# TOPCPCB.net
KiCad netlist of a schematic drawn in EAGLE
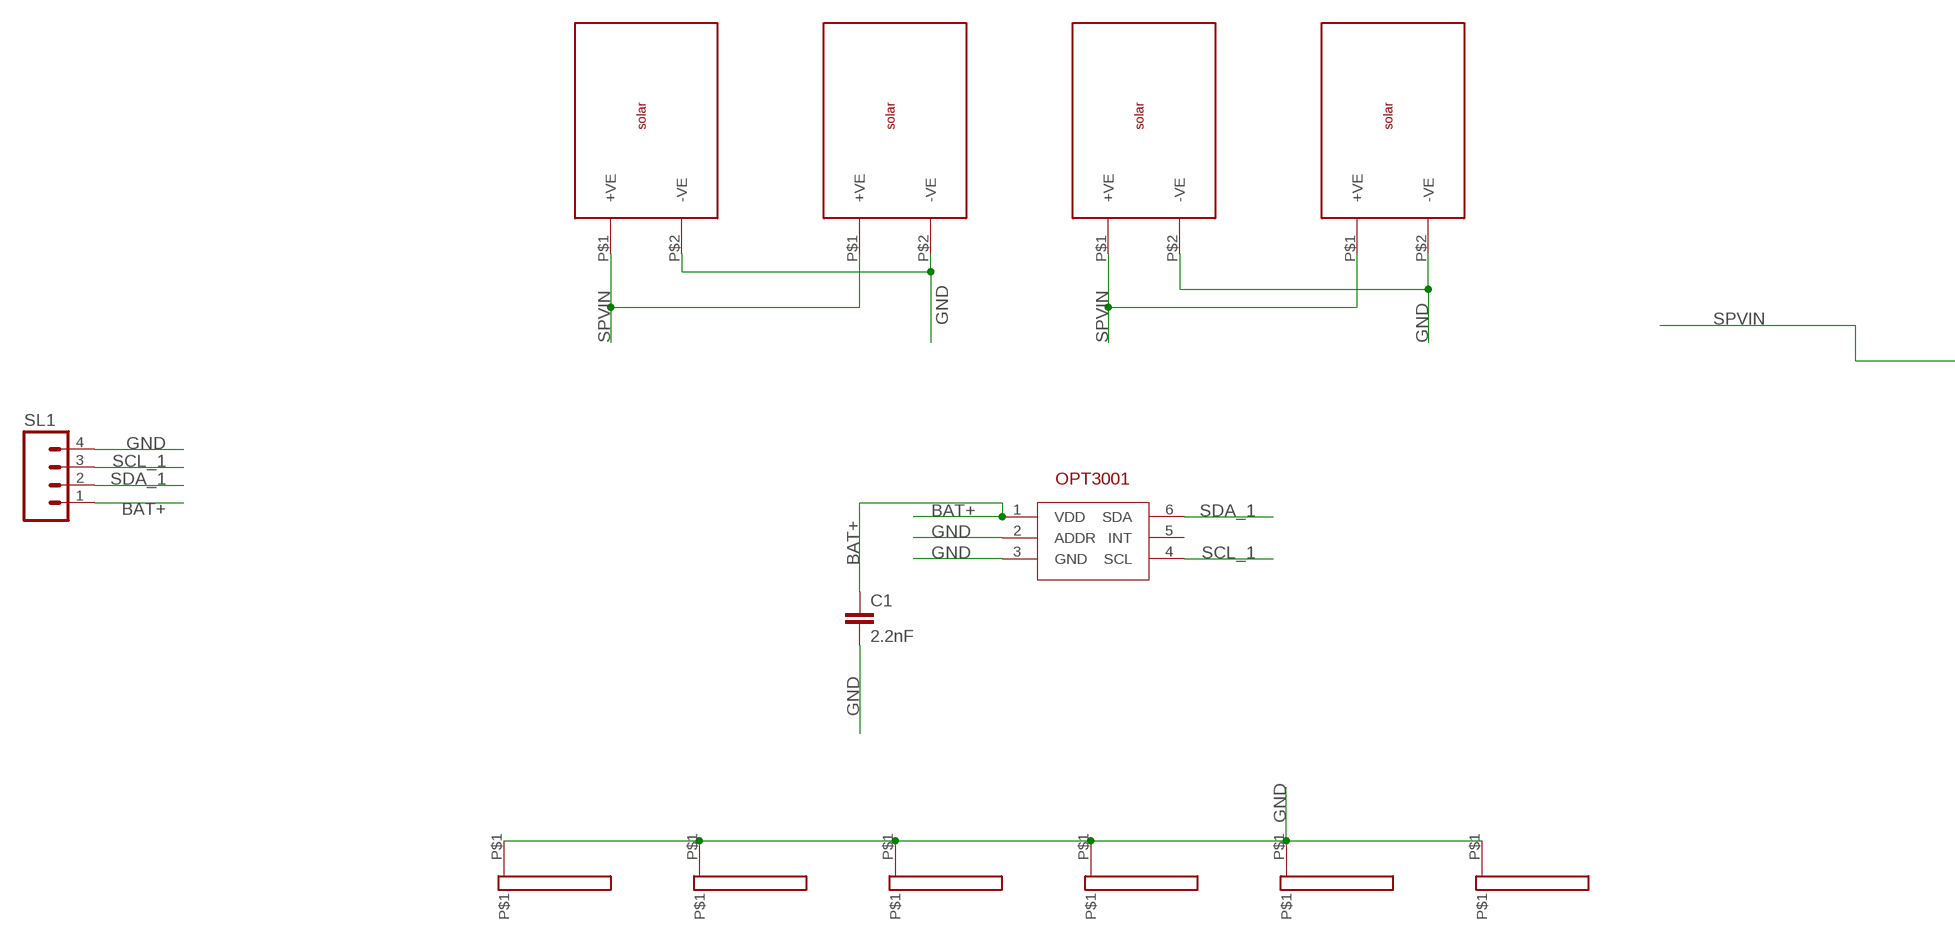
[diagram p0: schematic, sheet 1, part 1 of 2]
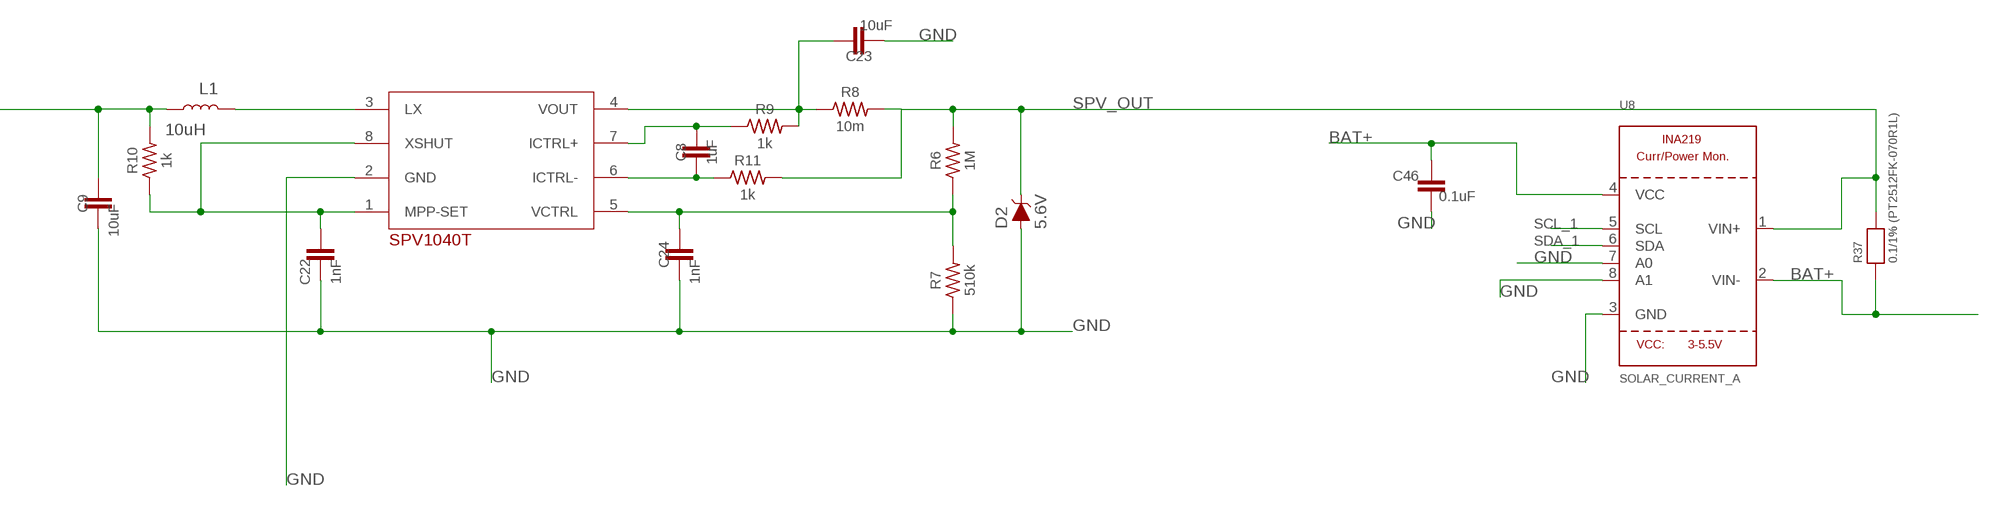
[diagram p1: schematic, sheet 1, part 2 of 2]

(export (version "E")
  (design (tool "Eeschema 10.0.6"))
  (components
    (comp (ref "C1")
      (value "2.2nF")
      (footprint "eagle-import:0603")
      (libsource (lib "eagle-import") (part "2.2NF/2200PF-0603-50V-10%"))
    )
    (comp (ref "C8")
      (value "1uF")
      (footprint "eagle-import:0603")
      (libsource (lib "eagle-import") (part "10UF-0603-6.3V-20%"))
    )
    (comp (ref "C9")
      (value "10uF")
      (footprint "eagle-import:0603")
      (libsource (lib "eagle-import") (part "10UF-0603-6.3V-20%"))
    )
    (comp (ref "C22")
      (value "1nF")
      (footprint "eagle-import:0603")
      (libsource (lib "eagle-import") (part "10UF-0603-6.3V-20%"))
    )
    (comp (ref "C23")
      (value "10uF")
      (footprint "eagle-import:0603")
      (libsource (lib "eagle-import") (part "10UF-0603-6.3V-20%"))
    )
    (comp (ref "C24")
      (value "1nF")
      (footprint "eagle-import:0603")
      (libsource (lib "eagle-import") (part "10UF-0603-6.3V-20%"))
    )
    (comp (ref "C46")
      (value "0.1uF")
      (footprint "eagle-import:0603")
      (libsource (lib "eagle-import") (part "10UF-0603-6.3V-20%"))
    )
    (comp (ref "D2")
      (value "5.6V")
      (footprint "eagle-import:SOD-323")
      (libsource (lib "eagle-import") (part "DIODE-ZENER-MMSZ5232BS"))
    )
    (comp (ref "L1")
      (value "10uH")
      (footprint "eagle-import:0603")
      (libsource (lib "eagle-import") (part "INDUCTOR-0603-33NH"))
    )
    (comp (ref "LEFTSOLD")
      (value "16X2")
      (footprint "eagle-import:16X2")
      (libsource (lib "eagle-import") (part "16X2"))
    )
    (comp (ref "R6")
      (value "1M")
      (footprint "eagle-import:RES_0603")
      (fields
        (field (name "DIGIKEY_PART_NUMBER") "311-0.0GRTR-ND")
        (field (name "MANUFACTURER") "Yageo")
        (field (name "MPN") "RC0603JR-070RL")
        (field (name "CREATED_BY") "PCBLayout.com")
      )
      (libsource (lib "eagle-import") (part "RC0603JR-070RL"))
    )
    (comp (ref "R7")
      (value "510k")
      (footprint "eagle-import:RES_0603")
      (fields
        (field (name "DIGIKEY_PART_NUMBER") "311-0.0GRTR-ND")
        (field (name "MANUFACTURER") "Yageo")
        (field (name "MPN") "RC0603JR-070RL")
        (field (name "CREATED_BY") "PCBLayout.com")
      )
      (libsource (lib "eagle-import") (part "RC0603JR-070RL"))
    )
    (comp (ref "R8")
      (value "10m")
      (footprint "eagle-import:RES_0603")
      (fields
        (field (name "DIGIKEY_PART_NUMBER") "311-0.0GRTR-ND")
        (field (name "MANUFACTURER") "Yageo")
        (field (name "MPN") "RC0603JR-070RL")
        (field (name "CREATED_BY") "PCBLayout.com")
      )
      (libsource (lib "eagle-import") (part "RC0603JR-070RL"))
    )
    (comp (ref "R9")
      (value "1k")
      (footprint "eagle-import:RES_0603")
      (fields
        (field (name "DIGIKEY_PART_NUMBER") "311-0.0GRTR-ND")
        (field (name "MANUFACTURER") "Yageo")
        (field (name "MPN") "RC0603JR-070RL")
        (field (name "CREATED_BY") "PCBLayout.com")
      )
      (libsource (lib "eagle-import") (part "RC0603JR-070RL"))
    )
    (comp (ref "R10")
      (value "1k")
      (footprint "eagle-import:RES_0603")
      (fields
        (field (name "DIGIKEY_PART_NUMBER") "311-0.0GRTR-ND")
        (field (name "MANUFACTURER") "Yageo")
        (field (name "MPN") "RC0603JR-070RL")
        (field (name "CREATED_BY") "PCBLayout.com")
      )
      (libsource (lib "eagle-import") (part "RC0603JR-070RL"))
    )
    (comp (ref "R11")
      (value "1k")
      (footprint "eagle-import:RES_0603")
      (fields
        (field (name "DIGIKEY_PART_NUMBER") "311-0.0GRTR-ND")
        (field (name "MANUFACTURER") "Yageo")
        (field (name "MPN") "RC0603JR-070RL")
        (field (name "CREATED_BY") "PCBLayout.com")
      )
      (libsource (lib "eagle-import") (part "RC0603JR-070RL"))
    )
    (comp (ref "R37")
      (value "0.1/1% (PT2512FK-070R1L)")
      (footprint "eagle-import:2512")
      (libsource (lib "eagle-import") (part "RESISTOR2512"))
    )
    (comp (ref "SL1")
      (value "M04")
      (footprint "eagle-import:04P")
      (libsource (lib "eagle-import") (part "M04"))
    )
    (comp (ref "SPV_A")
      (value "SPV1040T_")
      (footprint "eagle-import:SOP65P640X120-8N")
      (libsource (lib "eagle-import") (part "SPV1040T_"))
    )
    (comp (ref "U$1")
      (value "16X2")
      (footprint "eagle-import:16X2")
      (libsource (lib "eagle-import") (part "16X2"))
    )
    (comp (ref "U$4")
      (value "16X2")
      (footprint "eagle-import:16X2")
      (libsource (lib "eagle-import") (part "16X2"))
    )
    (comp (ref "U$5")
      (value "16X2")
      (footprint "eagle-import:16X2")
      (libsource (lib "eagle-import") (part "16X2"))
    )
    (comp (ref "U$7")
      (value "16X2")
      (footprint "eagle-import:16X2")
      (libsource (lib "eagle-import") (part "16X2"))
    )
    (comp (ref "U$9")
      (value "16X2")
      (footprint "eagle-import:16X2")
      (libsource (lib "eagle-import") (part "16X2"))
    )
    (comp (ref "U$10")
      (value "SOLAR_50_5_2")
      (footprint "eagle-import:FOOT")
      (libsource (lib "eagle-import") (part "SOLAR_50_5_2"))
    )
    (comp (ref "U$11")
      (value "SOLAR_50_5_2")
      (footprint "eagle-import:FOOT")
      (libsource (lib "eagle-import") (part "SOLAR_50_5_2"))
    )
    (comp (ref "U$12")
      (value "SOLAR_50_5_2")
      (footprint "eagle-import:FOOT")
      (libsource (lib "eagle-import") (part "SOLAR_50_5_2"))
    )
    (comp (ref "U$13")
      (value "SOLAR_50_5_2")
      (footprint "eagle-import:FOOT")
      (libsource (lib "eagle-import") (part "SOLAR_50_5_2"))
    )
    (comp (ref "U1")
      (value "SON65P200X200X65-7N")
      (footprint "eagle-import:SON65P200X200X65-7N")
      (fields (field (name "MANUFACTURER") "Maxim Integrated"))
      (libsource (lib "eagle-import") (part "SON65P200X200X65-7N"))
    )
    (comp (ref "U8")
      (value "SOLAR_CURRENT_A")
      (footprint "eagle-import:SOT23-8")
      (libsource (lib "eagle-import") (part "INA219"))
    )
  )
  (nets
    (net (code "1") (name "/BAT+") (class "Default")
      (node (ref "C1") (pin "1") (pinfunction "1_1") (pintype "passive"))
      (node (ref "C46") (pin "1") (pinfunction "1_1") (pintype "passive"))
      (node (ref "R37") (pin "1") (pinfunction "1_1") (pintype "passive"))
      (node (ref "SL1") (pin "1") (pinfunction "1_1") (pintype "passive"))
      (node (ref "U1") (pin "1") (pinfunction "VDD_1") (pintype "bidirectional"))
      (node (ref "U8") (pin "2") (pinfunction "VIN-_2") (pintype "bidirectional"))
      (node (ref "U8") (pin "4") (pinfunction "VCC_4") (pintype "bidirectional"))
    )
    (net (code "2") (name "/GND") (class "Default")
      (node (ref "C1") (pin "2") (pinfunction "2_2") (pintype "passive"))
      (node (ref "C22") (pin "2") (pinfunction "2_2") (pintype "passive"))
      (node (ref "C23") (pin "2") (pinfunction "2_2") (pintype "passive"))
      (node (ref "C24") (pin "2") (pinfunction "2_2") (pintype "passive"))
      (node (ref "C46") (pin "2") (pinfunction "2_2") (pintype "passive"))
      (node (ref "C9") (pin "2") (pinfunction "2_2") (pintype "passive"))
      (node (ref "D2") (pin "A") (pinfunction "A_A") (pintype "passive"))
      (node (ref "LEFTSOLD") (pin "P$1") (pinfunction "P$1_P$1") (pintype "bidirectional"))
      (node (ref "R7") (pin "1") (pinfunction "1_1") (pintype "passive"))
      (node (ref "SL1") (pin "4") (pinfunction "4_4") (pintype "passive"))
      (node (ref "SPV_A") (pin "2") (pinfunction "GND_2") (pintype "bidirectional"))
      (node (ref "U$1") (pin "P$1") (pinfunction "P$1_P$1") (pintype "bidirectional"))
      (node (ref "U$10") (pin "P$2") (pinfunction "-VE_P$2") (pintype "bidirectional"))
      (node (ref "U$11") (pin "P$2") (pinfunction "-VE_P$2") (pintype "bidirectional"))
      (node (ref "U$12") (pin "P$2") (pinfunction "-VE_P$2") (pintype "bidirectional"))
      (node (ref "U$13") (pin "P$2") (pinfunction "-VE_P$2") (pintype "bidirectional"))
      (node (ref "U$4") (pin "P$1") (pinfunction "P$1_P$1") (pintype "bidirectional"))
      (node (ref "U$5") (pin "P$1") (pinfunction "P$1_P$1") (pintype "bidirectional"))
      (node (ref "U$7") (pin "P$1") (pinfunction "P$1_P$1") (pintype "bidirectional"))
      (node (ref "U$9") (pin "P$1") (pinfunction "P$1_P$1") (pintype "bidirectional"))
      (node (ref "U1") (pin "2") (pinfunction "ADDR_2") (pintype "bidirectional"))
      (node (ref "U1") (pin "3") (pinfunction "GND_3") (pintype "bidirectional"))
      (node (ref "U8") (pin "3") (pinfunction "GND_3") (pintype "bidirectional"))
      (node (ref "U8") (pin "7") (pinfunction "A0_7") (pintype "bidirectional"))
      (node (ref "U8") (pin "8") (pinfunction "A1_8") (pintype "bidirectional"))
    )
    (net (code "3") (name "/SCL_1") (class "Default")
      (node (ref "SL1") (pin "3") (pinfunction "3_3") (pintype "passive"))
      (node (ref "U1") (pin "4") (pinfunction "SCL_4") (pintype "bidirectional"))
      (node (ref "U8") (pin "5") (pinfunction "SCL_5") (pintype "bidirectional"))
    )
    (net (code "4") (name "/SDA_1") (class "Default")
      (node (ref "SL1") (pin "2") (pinfunction "2_2") (pintype "passive"))
      (node (ref "U1") (pin "6") (pinfunction "SDA_6") (pintype "bidirectional"))
      (node (ref "U8") (pin "6") (pinfunction "SDA_6") (pintype "bidirectional"))
    )
    (net (code "5") (name "/SPVIN") (class "Default")
      (node (ref "C9") (pin "1") (pinfunction "1_1") (pintype "passive"))
      (node (ref "L1") (pin "1") (pinfunction "1_1") (pintype "passive"))
      (node (ref "R10") (pin "2") (pinfunction "2_2") (pintype "passive"))
      (node (ref "U$10") (pin "P$1") (pinfunction "+VE_P$1") (pintype "bidirectional"))
      (node (ref "U$11") (pin "P$1") (pinfunction "+VE_P$1") (pintype "bidirectional"))
      (node (ref "U$12") (pin "P$1") (pinfunction "+VE_P$1") (pintype "bidirectional"))
      (node (ref "U$13") (pin "P$1") (pinfunction "+VE_P$1") (pintype "bidirectional"))
    )
    (net (code "6") (name "/SPV_OUT") (class "Default")
      (node (ref "D2") (pin "C") (pinfunction "C_C") (pintype "passive"))
      (node (ref "R11") (pin "2") (pinfunction "2_2") (pintype "passive"))
      (node (ref "R37") (pin "2") (pinfunction "2_2") (pintype "passive"))
      (node (ref "R6") (pin "2") (pinfunction "2_2") (pintype "passive"))
      (node (ref "R8") (pin "2") (pinfunction "2_2") (pintype "passive"))
      (node (ref "U8") (pin "1") (pinfunction "VIN+_1") (pintype "bidirectional"))
    )
    (net (code "7") (name "Net-(SPV_A-ICTRL+)") (class "Default")
      (node (ref "C8") (pin "1") (pinfunction "1_1") (pintype "passive"))
      (node (ref "R9") (pin "1") (pinfunction "1_1") (pintype "passive"))
      (node (ref "SPV_A") (pin "7") (pinfunction "ICTRL+_7") (pintype "bidirectional"))
    )
    (net (code "8") (name "Net-(SPV_A-ICTRL-)") (class "Default")
      (node (ref "C8") (pin "2") (pinfunction "2_2") (pintype "passive"))
      (node (ref "R11") (pin "1") (pinfunction "1_1") (pintype "passive"))
      (node (ref "SPV_A") (pin "6") (pinfunction "ICTRL-_6") (pintype "bidirectional"))
    )
    (net (code "9") (name "Net-(SPV_A-LX)") (class "Default")
      (node (ref "L1") (pin "2") (pinfunction "2_2") (pintype "passive"))
      (node (ref "SPV_A") (pin "3") (pinfunction "LX_3") (pintype "bidirectional"))
    )
    (net (code "10") (name "Net-(SPV_A-MPP-SET)") (class "Default")
      (node (ref "C22") (pin "1") (pinfunction "1_1") (pintype "passive"))
      (node (ref "R10") (pin "1") (pinfunction "1_1") (pintype "passive"))
      (node (ref "SPV_A") (pin "1") (pinfunction "MPP-SET_1") (pintype "bidirectional"))
      (node (ref "SPV_A") (pin "8") (pinfunction "XSHUT_8") (pintype "bidirectional"))
    )
    (net (code "11") (name "Net-(SPV_A-VCTRL)") (class "Default")
      (node (ref "C24") (pin "1") (pinfunction "1_1") (pintype "passive"))
      (node (ref "R6") (pin "1") (pinfunction "1_1") (pintype "passive"))
      (node (ref "R7") (pin "2") (pinfunction "2_2") (pintype "passive"))
      (node (ref "SPV_A") (pin "5") (pinfunction "VCTRL_5") (pintype "bidirectional"))
    )
    (net (code "12") (name "Net-(SPV_A-VOUT)") (class "Default")
      (node (ref "C23") (pin "1") (pinfunction "1_1") (pintype "passive"))
      (node (ref "R8") (pin "1") (pinfunction "1_1") (pintype "passive"))
      (node (ref "R9") (pin "2") (pinfunction "2_2") (pintype "passive"))
      (node (ref "SPV_A") (pin "4") (pinfunction "VOUT_4") (pintype "bidirectional"))
    )
    (net (code "13") (name "unconnected-(U1-INT-Pad5)") (class "Default")
      (node (ref "U1") (pin "5") (pinfunction "INT_5") (pintype "bidirectional"))
    )
  )
)
